# SwitchNode.net
KiCad netlist of a schematic drawn in EAGLE
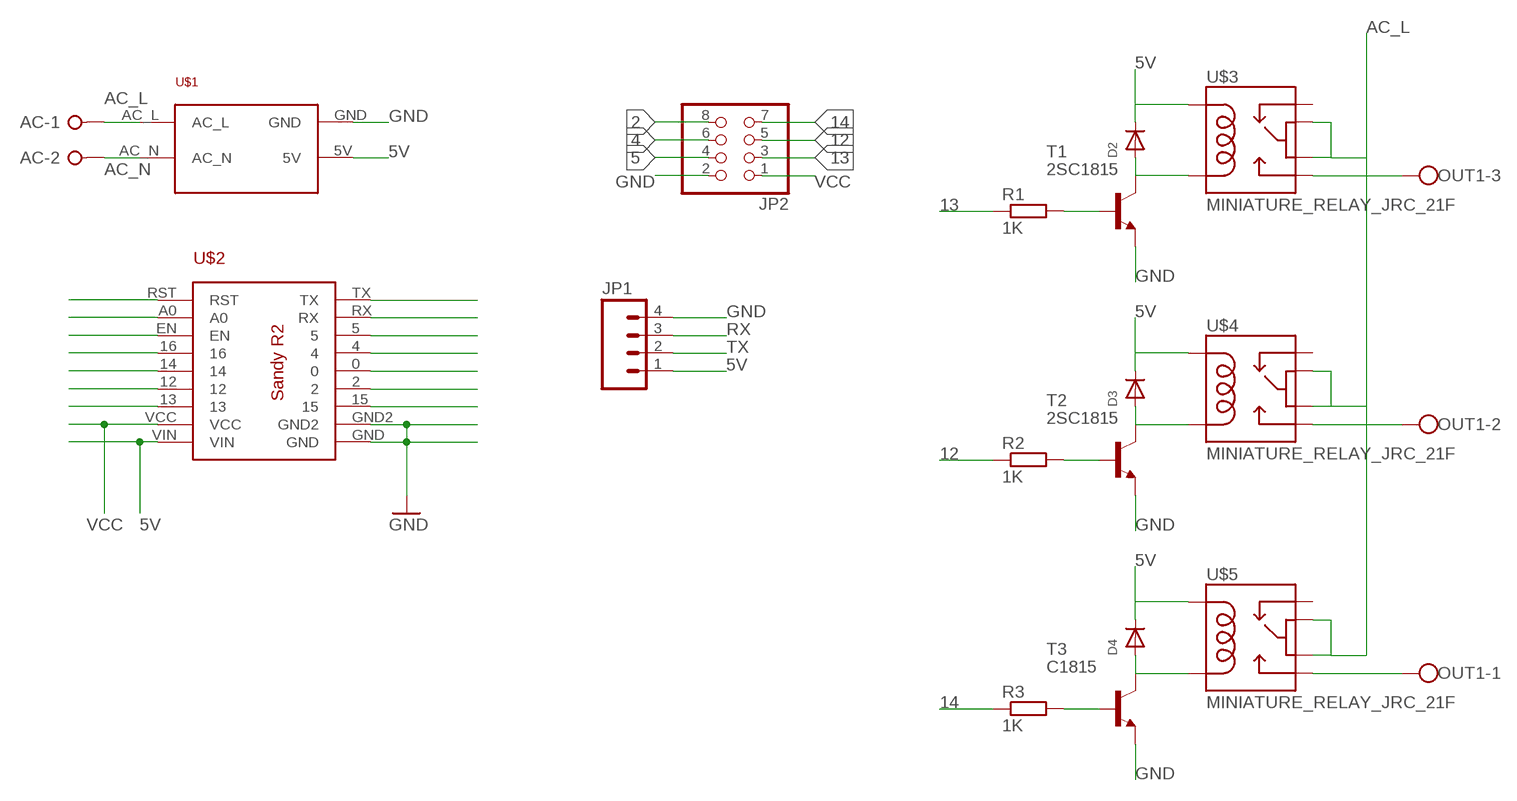
[diagram p0: schematic, sheet 1]

(export (version "E")
  (design (tool "Eeschema 10.0.6"))
  (components
    (comp (ref "AC")
      (value "W237-02P")
      (footprint "eagle-import:W237-132")
      (libsource (lib "eagle-import") (part "W237-02P"))
    )
    (comp (ref "D2")
      (value "DIODESMA")
      (footprint "eagle-import:SMADIODE")
      (libsource (lib "eagle-import") (part "DIODESMA"))
    )
    (comp (ref "D3")
      (value "DIODESMA")
      (footprint "eagle-import:SMADIODE")
      (libsource (lib "eagle-import") (part "DIODESMA"))
    )
    (comp (ref "D4")
      (value "DIODESMA")
      (footprint "eagle-import:SMADIODE")
      (libsource (lib "eagle-import") (part "DIODESMA"))
    )
    (comp (ref "JP1")
      (value "M04PTH")
      (footprint "eagle-import:1X04")
      (libsource (lib "eagle-import") (part "M04PTH"))
    )
    (comp (ref "JP2")
      (value "PINHD-2X4")
      (footprint "eagle-import:2X04")
      (libsource (lib "eagle-import") (part "PINHD-2X4"))
    )
    (comp (ref "OUT1")
      (value "W237-103")
      (footprint "eagle-import:W237-103")
      (fields (field (name "MPN") "237-103"))
      (libsource (lib "eagle-import") (part "W237-103"))
    )
    (comp (ref "R1")
      (value "1K")
      (footprint "eagle-import:R0805")
      (libsource (lib "eagle-import") (part "R-EU_R0805"))
    )
    (comp (ref "R2")
      (value "1K")
      (footprint "eagle-import:R0805")
      (libsource (lib "eagle-import") (part "R-EU_R0805"))
    )
    (comp (ref "R3")
      (value "1K")
      (footprint "eagle-import:R0805")
      (libsource (lib "eagle-import") (part "R-EU_R0805"))
    )
    (comp (ref "T1")
      (value "2SC1815")
      (footprint "eagle-import:TO92-ECB")
      (libsource (lib "eagle-import") (part "2SC1815"))
    )
    (comp (ref "T2")
      (value "2SC1815")
      (footprint "eagle-import:TO92-ECB")
      (libsource (lib "eagle-import") (part "2SC1815"))
    )
    (comp (ref "T3")
      (value "C1815")
      (footprint "eagle-import:TO92-ECB")
      (libsource (lib "eagle-import") (part "2SC1815"))
    )
    (comp (ref "U$1")
      (value "POWER_SUPPLY_220VAC_5V")
      (footprint "eagle-import:POWER_SUPPLY_220VAC_5V")
      (libsource (lib "eagle-import") (part "POWER_SUPPLY_220VAC_5V"))
    )
    (comp (ref "U$2")
      (value "MINI-ESP")
      (footprint "eagle-import:MINI-ESP")
      (libsource (lib "eagle-import") (part "MINI-ESP"))
    )
    (comp (ref "U$3")
      (value "MINIATURE_RELAY_JRC_21F")
      (footprint "eagle-import:MINIATURE_RELAY_JRC_21F")
      (libsource (lib "eagle-import") (part "MINIATURE_RELAY_JRC_21F"))
    )
    (comp (ref "U$4")
      (value "MINIATURE_RELAY_JRC_21F")
      (footprint "eagle-import:MINIATURE_RELAY_JRC_21F")
      (libsource (lib "eagle-import") (part "MINIATURE_RELAY_JRC_21F"))
    )
    (comp (ref "U$5")
      (value "MINIATURE_RELAY_JRC_21F")
      (footprint "eagle-import:MINIATURE_RELAY_JRC_21F")
      (libsource (lib "eagle-import") (part "MINIATURE_RELAY_JRC_21F"))
    )
  )
  (nets
    (net (code "1") (name "/5V") (class "Default")
      (node (ref "D2") (pin "C") (pinfunction "C_C") (pintype "passive"))
      (node (ref "D3") (pin "C") (pinfunction "C_C") (pintype "passive"))
      (node (ref "D4") (pin "C") (pinfunction "C_C") (pintype "passive"))
      (node (ref "JP1") (pin "1") (pinfunction "1_1") (pintype "passive"))
      (node (ref "U$1") (pin "5V") (pinfunction "5V_5V") (pintype "bidirectional"))
      (node (ref "U$2") (pin "VIN") (pinfunction "VIN_VIN") (pintype "bidirectional"))
      (node (ref "U$3") (pin "COIL1") (pinfunction "COIL1_COIL1") (pintype "bidirectional"))
      (node (ref "U$4") (pin "COIL1") (pinfunction "COIL1_COIL1") (pintype "bidirectional"))
      (node (ref "U$5") (pin "COIL1") (pinfunction "COIL1_COIL1") (pintype "bidirectional"))
    )
    (net (code "2") (name "/AC_L") (class "Default")
      (node (ref "AC") (pin "1") (pinfunction "KL_1") (pintype "passive"))
      (node (ref "U$1") (pin "AC_L") (pinfunction "AC_L_AC_L") (pintype "bidirectional"))
      (node (ref "U$3") (pin "COM1") (pinfunction "COM1_COM1") (pintype "bidirectional"))
      (node (ref "U$3") (pin "COM2") (pinfunction "COM2_COM2") (pintype "bidirectional"))
      (node (ref "U$4") (pin "COM1") (pinfunction "COM1_COM1") (pintype "bidirectional"))
      (node (ref "U$4") (pin "COM2") (pinfunction "COM2_COM2") (pintype "bidirectional"))
      (node (ref "U$5") (pin "COM1") (pinfunction "COM1_COM1") (pintype "bidirectional"))
      (node (ref "U$5") (pin "COM2") (pinfunction "COM2_COM2") (pintype "bidirectional"))
    )
    (net (code "3") (name "/AC_N") (class "Default")
      (node (ref "AC") (pin "2") (pinfunction "KL_2") (pintype "passive"))
      (node (ref "U$1") (pin "AC_N") (pinfunction "AC_N_AC_N") (pintype "bidirectional"))
    )
    (net (code "4") (name "/RX") (class "Default")
      (node (ref "JP1") (pin "3") (pinfunction "3_3") (pintype "passive"))
      (node (ref "U$2") (pin "RX") (pinfunction "RX_RX") (pintype "bidirectional"))
    )
    (net (code "5") (name "/TX") (class "Default")
      (node (ref "JP1") (pin "2") (pinfunction "2_2") (pintype "passive"))
      (node (ref "U$2") (pin "TX") (pinfunction "TX_TX") (pintype "bidirectional"))
    )
    (net (code "6") (name "/VCC") (class "Default")
      (node (ref "JP2") (pin "1") (pinfunction "1_1") (pintype "passive"))
      (node (ref "U$2") (pin "VCC") (pinfunction "VCC_VCC") (pintype "bidirectional"))
    )
    (net (code "7") (name "2") (class "Default")
      (node (ref "JP2") (pin "8") (pinfunction "8_8") (pintype "passive"))
      (node (ref "U$2") (pin "2") (pinfunction "2_2") (pintype "bidirectional"))
    )
    (net (code "8") (name "4") (class "Default")
      (node (ref "JP2") (pin "6") (pinfunction "6_6") (pintype "passive"))
      (node (ref "U$2") (pin "4") (pinfunction "4_4") (pintype "bidirectional"))
    )
    (net (code "9") (name "5") (class "Default")
      (node (ref "JP2") (pin "4") (pinfunction "4_4") (pintype "passive"))
      (node (ref "U$2") (pin "5") (pinfunction "5_5") (pintype "bidirectional"))
    )
    (net (code "10") (name "12") (class "Default")
      (node (ref "JP2") (pin "5") (pinfunction "5_5") (pintype "passive"))
      (node (ref "R2") (pin "1") (pinfunction "1_1") (pintype "passive"))
      (node (ref "U$2") (pin "12") (pinfunction "12_12") (pintype "bidirectional"))
    )
    (net (code "11") (name "13") (class "Default")
      (node (ref "JP2") (pin "3") (pinfunction "3_3") (pintype "passive"))
      (node (ref "R1") (pin "1") (pinfunction "1_1") (pintype "passive"))
      (node (ref "U$2") (pin "13") (pinfunction "13_13") (pintype "bidirectional"))
    )
    (net (code "12") (name "14") (class "Default")
      (node (ref "JP2") (pin "7") (pinfunction "7_7") (pintype "passive"))
      (node (ref "R3") (pin "1") (pinfunction "1_1") (pintype "passive"))
      (node (ref "U$2") (pin "14") (pinfunction "14_14") (pintype "bidirectional"))
    )
    (net (code "13") (name "GND") (class "Default")
      (node (ref "JP1") (pin "4") (pinfunction "4_4") (pintype "passive"))
      (node (ref "JP2") (pin "2") (pinfunction "2_2") (pintype "passive"))
      (node (ref "T1") (pin "E") (pinfunction "E_E") (pintype "passive"))
      (node (ref "T2") (pin "E") (pinfunction "E_E") (pintype "passive"))
      (node (ref "T3") (pin "E") (pinfunction "E_E") (pintype "passive"))
      (node (ref "U$1") (pin "GND") (pinfunction "GND_GND") (pintype "bidirectional"))
      (node (ref "U$2") (pin "GND") (pinfunction "GND_GND") (pintype "bidirectional"))
      (node (ref "U$2") (pin "GND2") (pinfunction "GND2_GND2") (pintype "bidirectional"))
    )
    (net (code "14") (name "Net-(D2-PadA)") (class "Default")
      (node (ref "D2") (pin "A") (pinfunction "A_A") (pintype "passive"))
      (node (ref "T1") (pin "C") (pinfunction "C_C") (pintype "passive"))
      (node (ref "U$3") (pin "COIL2") (pinfunction "COIL2_COIL2") (pintype "bidirectional"))
    )
    (net (code "15") (name "Net-(D3-PadA)") (class "Default")
      (node (ref "D3") (pin "A") (pinfunction "A_A") (pintype "passive"))
      (node (ref "T2") (pin "C") (pinfunction "C_C") (pintype "passive"))
      (node (ref "U$4") (pin "COIL2") (pinfunction "COIL2_COIL2") (pintype "bidirectional"))
    )
    (net (code "16") (name "Net-(D4-PadA)") (class "Default")
      (node (ref "D4") (pin "A") (pinfunction "A_A") (pintype "passive"))
      (node (ref "T3") (pin "C") (pinfunction "C_C") (pintype "passive"))
      (node (ref "U$5") (pin "COIL2") (pinfunction "COIL2_COIL2") (pintype "bidirectional"))
    )
    (net (code "17") (name "Net-(OUT1A-KL)") (class "Default")
      (node (ref "OUT1") (pin "1") (pinfunction "KL_1") (pintype "passive"))
      (node (ref "U$5") (pin "NO") (pinfunction "NO_NO") (pintype "bidirectional"))
    )
    (net (code "18") (name "Net-(OUT1B-KL)") (class "Default")
      (node (ref "OUT1") (pin "2") (pinfunction "KL_2") (pintype "passive"))
      (node (ref "U$4") (pin "NO") (pinfunction "NO_NO") (pintype "bidirectional"))
    )
    (net (code "19") (name "Net-(OUT1C-KL)") (class "Default")
      (node (ref "OUT1") (pin "3") (pinfunction "KL_3") (pintype "passive"))
      (node (ref "U$3") (pin "NO") (pinfunction "NO_NO") (pintype "bidirectional"))
    )
    (net (code "20") (name "Net-(R1-Pad2)") (class "Default")
      (node (ref "R1") (pin "2") (pinfunction "2_2") (pintype "passive"))
      (node (ref "T1") (pin "B") (pinfunction "B_B") (pintype "passive"))
    )
    (net (code "21") (name "Net-(R2-Pad2)") (class "Default")
      (node (ref "R2") (pin "2") (pinfunction "2_2") (pintype "passive"))
      (node (ref "T2") (pin "B") (pinfunction "B_B") (pintype "passive"))
    )
    (net (code "22") (name "Net-(R3-Pad2)") (class "Default")
      (node (ref "R3") (pin "2") (pinfunction "2_2") (pintype "passive"))
      (node (ref "T3") (pin "B") (pinfunction "B_B") (pintype "passive"))
    )
    (net (code "23") (name "unconnected-(U$2-Pad0)") (class "Default")
      (node (ref "U$2") (pin "0") (pinfunction "0_0") (pintype "bidirectional"))
    )
    (net (code "24") (name "unconnected-(U$2-Pad15)") (class "Default")
      (node (ref "U$2") (pin "15") (pinfunction "15_15") (pintype "bidirectional"))
    )
    (net (code "25") (name "unconnected-(U$2-Pad16)") (class "Default")
      (node (ref "U$2") (pin "16") (pinfunction "16_16") (pintype "bidirectional"))
    )
    (net (code "26") (name "unconnected-(U$2-PadA0)") (class "Default")
      (node (ref "U$2") (pin "A0") (pinfunction "A0_A0") (pintype "bidirectional"))
    )
    (net (code "27") (name "unconnected-(U$2-PadEN)") (class "Default")
      (node (ref "U$2") (pin "EN") (pinfunction "EN_EN") (pintype "bidirectional"))
    )
    (net (code "28") (name "unconnected-(U$2-PadRST)") (class "Default")
      (node (ref "U$2") (pin "RST") (pinfunction "RST_RST") (pintype "bidirectional"))
    )
    (net (code "29") (name "unconnected-(U$3-PadNC)") (class "Default")
      (node (ref "U$3") (pin "NC") (pinfunction "NC_NC") (pintype "bidirectional"))
    )
    (net (code "30") (name "unconnected-(U$4-PadNC)") (class "Default")
      (node (ref "U$4") (pin "NC") (pinfunction "NC_NC") (pintype "bidirectional"))
    )
    (net (code "31") (name "unconnected-(U$5-PadNC)") (class "Default")
      (node (ref "U$5") (pin "NC") (pinfunction "NC_NC") (pintype "bidirectional"))
    )
  )
)
